# SparkFun_6DoF_ISM330DHCX_Micro.net
KiCad netlist of a schematic drawn in EAGLE
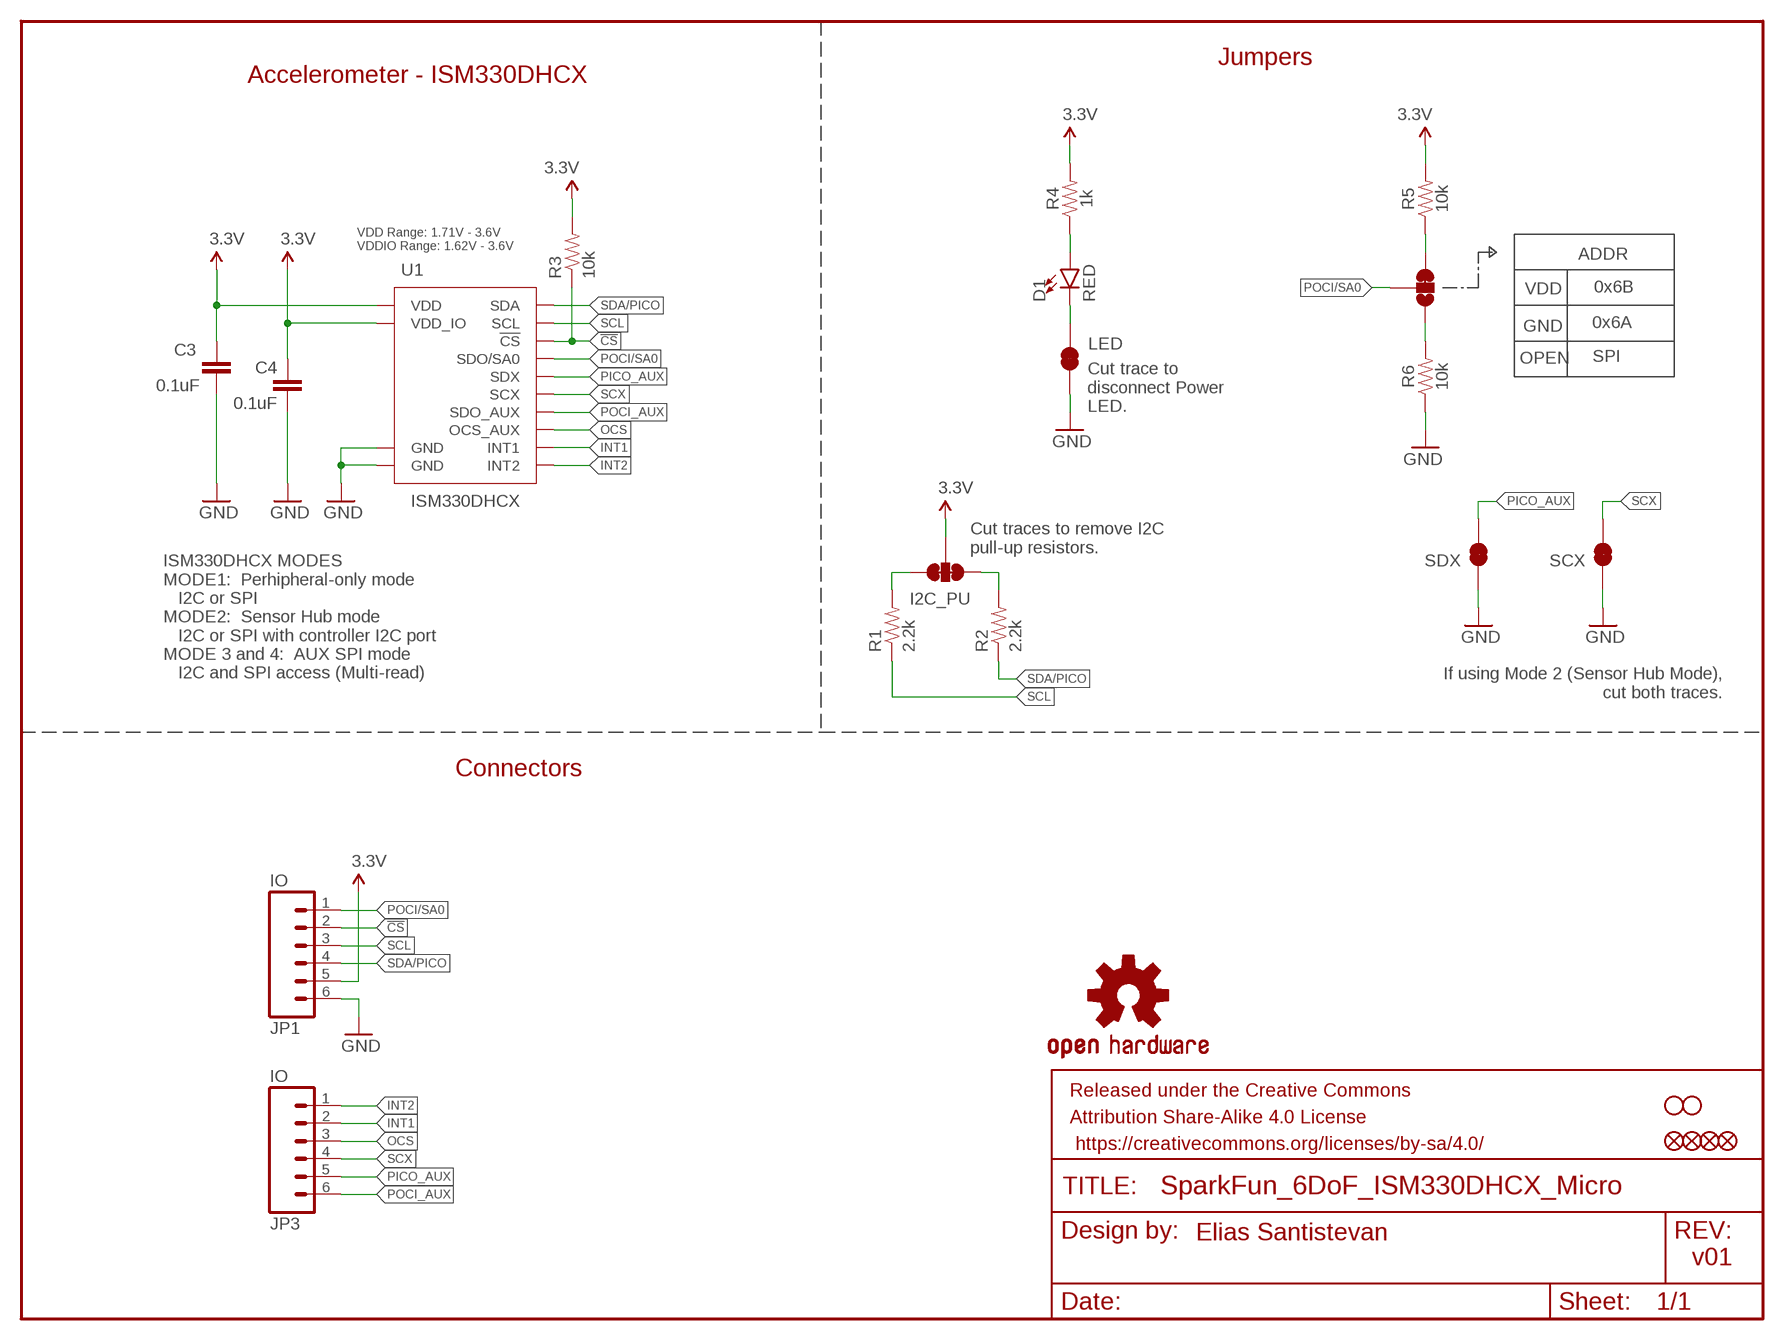
[diagram p0: schematic, sheet 1]

(export (version "E")
  (design (tool "Eeschema 10.0.6"))
  (components
    (comp (ref "ADDR")
      (value "JUMPER-SMT_3_1-NC_TRACE_SILK")
      (footprint "eagle-import:SMT-JUMPER_3_1-NC_TRACE_SILK")
      (libsource (lib "eagle-import") (part "JUMPER-SMT_3_1-NC_TRACE_SILK"))
    )
    (comp (ref "C3")
      (value "0.1uF")
      (footprint "eagle-import:0402-TIGHT")
      (libsource (lib "eagle-import") (part "0.1UF-0402T-6.3V-10%-X7R"))
    )
    (comp (ref "C4")
      (value "0.1uF")
      (footprint "eagle-import:0402-TIGHT")
      (libsource (lib "eagle-import") (part "0.1UF-0402T-6.3V-10%-X7R"))
    )
    (comp (ref "D1")
      (value "RED")
      (footprint "eagle-import:LED-0603")
      (libsource (lib "eagle-import") (part "LED-RED0603"))
    )
    (comp (ref "FD1")
      (value "FIDUCIALUFIDUCIAL")
      (footprint "eagle-import:FIDUCIAL-MICRO")
      (libsource (lib "eagle-import") (part "FIDUCIALUFIDUCIAL"))
    )
    (comp (ref "FD2")
      (value "FIDUCIALUFIDUCIAL")
      (footprint "eagle-import:FIDUCIAL-MICRO")
      (libsource (lib "eagle-import") (part "FIDUCIALUFIDUCIAL"))
    )
    (comp (ref "FID1")
      (value "FIDUCIALUFIDUCIAL")
      (footprint "eagle-import:FIDUCIAL-MICRO")
      (libsource (lib "eagle-import") (part "FIDUCIALUFIDUCIAL"))
    )
    (comp (ref "FID2")
      (value "FIDUCIALUFIDUCIAL")
      (footprint "eagle-import:FIDUCIAL-MICRO")
      (libsource (lib "eagle-import") (part "FIDUCIALUFIDUCIAL"))
    )
    (comp (ref "FRAME1")
      (value "FRAME-LETTER")
      (footprint "eagle-import:CREATIVE_COMMONS")
      (fields (field (name "DESIGNER") "Elias Santistevan"))
      (libsource (lib "eagle-import") (part "FRAME-LETTER"))
    )
    (comp (ref "I2C_PU")
      (value "S_MODE")
      (footprint "eagle-import:SMT-JUMPER_3_2-NC_TRACE_SILK")
      (libsource (lib "eagle-import") (part "JUMPER-SMT_3_2-NC_TRACE_SILK"))
    )
    (comp (ref "JP1")
      (value "IO")
      (footprint "eagle-import:1X06_NO_SILK")
      (libsource (lib "eagle-import") (part "CONN_06NO_SILK_NO_POP"))
    )
    (comp (ref "JP3")
      (value "IO")
      (footprint "eagle-import:1X06_NO_SILK")
      (libsource (lib "eagle-import") (part "CONN_06NO_SILK_NO_POP"))
    )
    (comp (ref "LED")
      (value "JUMPER-SMT_2_NC_TRACE_SILK")
      (footprint "eagle-import:SMT-JUMPER_2_NC_TRACE_SILK")
      (libsource (lib "eagle-import") (part "JUMPER-SMT_2_NC_TRACE_SILK"))
    )
    (comp (ref "LOGO2")
      (value "OSHW-LOGOMINI")
      (footprint "eagle-import:OSHW-LOGO-MINI")
      (libsource (lib "eagle-import") (part "OSHW-LOGOMINI"))
    )
    (comp (ref "R1")
      (value "2.2k")
      (footprint "eagle-import:0402-TIGHT")
      (libsource (lib "eagle-import") (part "2.2KOHM-0402T-1/16W-1%"))
    )
    (comp (ref "R2")
      (value "2.2k")
      (footprint "eagle-import:0402-TIGHT")
      (libsource (lib "eagle-import") (part "2.2KOHM-0402T-1/16W-1%"))
    )
    (comp (ref "R3")
      (value "10k")
      (footprint "eagle-import:0402-TIGHT")
      (libsource (lib "eagle-import") (part "10KOHM-0402T-1/16W-1%"))
    )
    (comp (ref "R4")
      (value "1k")
      (footprint "eagle-import:0402-TIGHT")
      (libsource (lib "eagle-import") (part "1KOHM-0402T-1/16W-1%"))
    )
    (comp (ref "R5")
      (value "10k")
      (footprint "eagle-import:0402-TIGHT")
      (libsource (lib "eagle-import") (part "10KOHM-0402T-1/16W-1%"))
    )
    (comp (ref "R6")
      (value "10k")
      (footprint "eagle-import:0402-TIGHT")
      (libsource (lib "eagle-import") (part "10KOHM-0402T-1/16W-1%"))
    )
    (comp (ref "SCX")
      (value "JUMPER-SMT_2_NC_TRACE_SILK")
      (footprint "eagle-import:SMT-JUMPER_2_NC_TRACE_SILK")
      (libsource (lib "eagle-import") (part "JUMPER-SMT_2_NC_TRACE_SILK"))
    )
    (comp (ref "SDX")
      (value "JUMPER-SMT_2_NC_TRACE_SILK")
      (footprint "eagle-import:SMT-JUMPER_2_NC_TRACE_SILK")
      (libsource (lib "eagle-import") (part "JUMPER-SMT_2_NC_TRACE_SILK"))
    )
    (comp (ref "STANDOFF1")
      (value "STAND-OFFTIGHT")
      (footprint "eagle-import:STAND-OFF-TIGHT")
      (libsource (lib "eagle-import") (part "STAND-OFFTIGHT"))
    )
    (comp (ref "STANDOFF2")
      (value "STAND-OFFTIGHT")
      (footprint "eagle-import:STAND-OFF-TIGHT")
      (libsource (lib "eagle-import") (part "STAND-OFFTIGHT"))
    )
    (comp (ref "U1")
      (value "ISM330DHCX")
      (footprint "eagle-import:LGA-14L")
      (libsource (lib "eagle-import") (part "ISM330DHCX"))
    )
  )
  (nets
    (net (code "1") (name "/~{CS}") (class "Default")
      (node (ref "JP1") (pin "2") (pinfunction "2_2") (pintype "passive"))
      (node (ref "R3") (pin "1") (pinfunction "1_1") (pintype "passive"))
      (node (ref "U1") (pin "P12") (pinfunction "~{CS}_P12") (pintype "bidirectional"))
    )
    (net (code "2") (name "3.3V") (class "Default")
      (node (ref "C3") (pin "1") (pinfunction "1_1") (pintype "passive"))
      (node (ref "C4") (pin "1") (pinfunction "1_1") (pintype "passive"))
      (node (ref "I2C_PU") (pin "2") (pinfunction "2_2") (pintype "passive"))
      (node (ref "JP1") (pin "5") (pinfunction "5_5") (pintype "passive"))
      (node (ref "R3") (pin "2") (pinfunction "2_2") (pintype "passive"))
      (node (ref "R4") (pin "2") (pinfunction "2_2") (pintype "passive"))
      (node (ref "R5") (pin "2") (pinfunction "2_2") (pintype "passive"))
      (node (ref "U1") (pin "P5") (pinfunction "VDD_IO_P5") (pintype "power_in"))
      (node (ref "U1") (pin "P8") (pinfunction "VDD_P8") (pintype "power_in"))
    )
    (net (code "3") (name "GND") (class "Default")
      (node (ref "C3") (pin "2") (pinfunction "2_2") (pintype "passive"))
      (node (ref "C4") (pin "2") (pinfunction "2_2") (pintype "passive"))
      (node (ref "JP1") (pin "6") (pinfunction "6_6") (pintype "passive"))
      (node (ref "LED") (pin "1") (pinfunction "1_1") (pintype "passive"))
      (node (ref "R6") (pin "1") (pinfunction "1_1") (pintype "passive"))
      (node (ref "SCX") (pin "1") (pinfunction "1_1") (pintype "passive"))
      (node (ref "SDX") (pin "1") (pinfunction "1_1") (pintype "passive"))
      (node (ref "U1") (pin "P6") (pinfunction "GND_P6") (pintype "power_in"))
      (node (ref "U1") (pin "P7") (pinfunction "GND_P7") (pintype "power_in"))
    )
    (net (code "4") (name "INT1") (class "Default")
      (node (ref "JP3") (pin "2") (pinfunction "2_2") (pintype "passive"))
      (node (ref "U1") (pin "P4") (pinfunction "INT1_P4") (pintype "bidirectional"))
    )
    (net (code "5") (name "INT2") (class "Default")
      (node (ref "JP3") (pin "1") (pinfunction "1_1") (pintype "passive"))
      (node (ref "U1") (pin "P9") (pinfunction "INT2_P9") (pintype "bidirectional"))
    )
    (net (code "6") (name "Net-(ADDR-Pad1)") (class "Default")
      (node (ref "ADDR") (pin "1") (pinfunction "1_1") (pintype "passive"))
      (node (ref "R6") (pin "2") (pinfunction "2_2") (pintype "passive"))
    )
    (net (code "7") (name "Net-(ADDR-Pad3)") (class "Default")
      (node (ref "ADDR") (pin "3") (pinfunction "3_3") (pintype "passive"))
      (node (ref "R5") (pin "1") (pinfunction "1_1") (pintype "passive"))
    )
    (net (code "8") (name "Net-(D1-PadA)") (class "Default")
      (node (ref "D1") (pin "A") (pinfunction "A_A") (pintype "passive"))
      (node (ref "R4") (pin "1") (pinfunction "1_1") (pintype "passive"))
    )
    (net (code "9") (name "Net-(D1-PadC)") (class "Default")
      (node (ref "D1") (pin "C") (pinfunction "C_C") (pintype "passive"))
      (node (ref "LED") (pin "2") (pinfunction "2_2") (pintype "passive"))
    )
    (net (code "10") (name "Net-(I2C_PU-Pad1)") (class "Default")
      (node (ref "I2C_PU") (pin "1") (pinfunction "1_1") (pintype "passive"))
      (node (ref "R1") (pin "2") (pinfunction "2_2") (pintype "passive"))
    )
    (net (code "11") (name "Net-(I2C_PU-Pad3)") (class "Default")
      (node (ref "I2C_PU") (pin "3") (pinfunction "3_3") (pintype "passive"))
      (node (ref "R2") (pin "2") (pinfunction "2_2") (pintype "passive"))
    )
    (net (code "12") (name "OCS") (class "Default")
      (node (ref "JP3") (pin "3") (pinfunction "3_3") (pintype "passive"))
      (node (ref "U1") (pin "P10") (pinfunction "OCS_AUX_P10") (pintype "bidirectional"))
    )
    (net (code "13") (name "PICO_AUX") (class "Default")
      (node (ref "JP3") (pin "5") (pinfunction "5_5") (pintype "passive"))
      (node (ref "SDX") (pin "2") (pinfunction "2_2") (pintype "passive"))
      (node (ref "U1") (pin "P2") (pinfunction "SDX_P2") (pintype "bidirectional"))
    )
    (net (code "14") (name "POCI_AUX") (class "Default")
      (node (ref "JP3") (pin "6") (pinfunction "6_6") (pintype "passive"))
      (node (ref "U1") (pin "P11") (pinfunction "SDO_AUX_P11") (pintype "bidirectional"))
    )
    (net (code "15") (name "POCI{slash}SA0") (class "Default")
      (node (ref "ADDR") (pin "2") (pinfunction "2_2") (pintype "passive"))
      (node (ref "JP1") (pin "1") (pinfunction "1_1") (pintype "passive"))
      (node (ref "U1") (pin "P1") (pinfunction "SDO/SA0_P1") (pintype "bidirectional"))
    )
    (net (code "16") (name "SCL") (class "Default")
      (node (ref "JP1") (pin "3") (pinfunction "3_3") (pintype "passive"))
      (node (ref "R1") (pin "1") (pinfunction "1_1") (pintype "passive"))
      (node (ref "U1") (pin "P13") (pinfunction "SCL_P13") (pintype "bidirectional"))
    )
    (net (code "17") (name "SCX") (class "Default")
      (node (ref "JP3") (pin "4") (pinfunction "4_4") (pintype "passive"))
      (node (ref "SCX") (pin "2") (pinfunction "2_2") (pintype "passive"))
      (node (ref "U1") (pin "P3") (pinfunction "SCX_P3") (pintype "bidirectional"))
    )
    (net (code "18") (name "SDA{slash}PICO") (class "Default")
      (node (ref "JP1") (pin "4") (pinfunction "4_4") (pintype "passive"))
      (node (ref "R2") (pin "1") (pinfunction "1_1") (pintype "passive"))
      (node (ref "U1") (pin "P14") (pinfunction "SDA_P14") (pintype "bidirectional"))
    )
  )
)
